# SN74LVC1G86.net
KiCad netlist of a schematic drawn in EasyEDA Pro
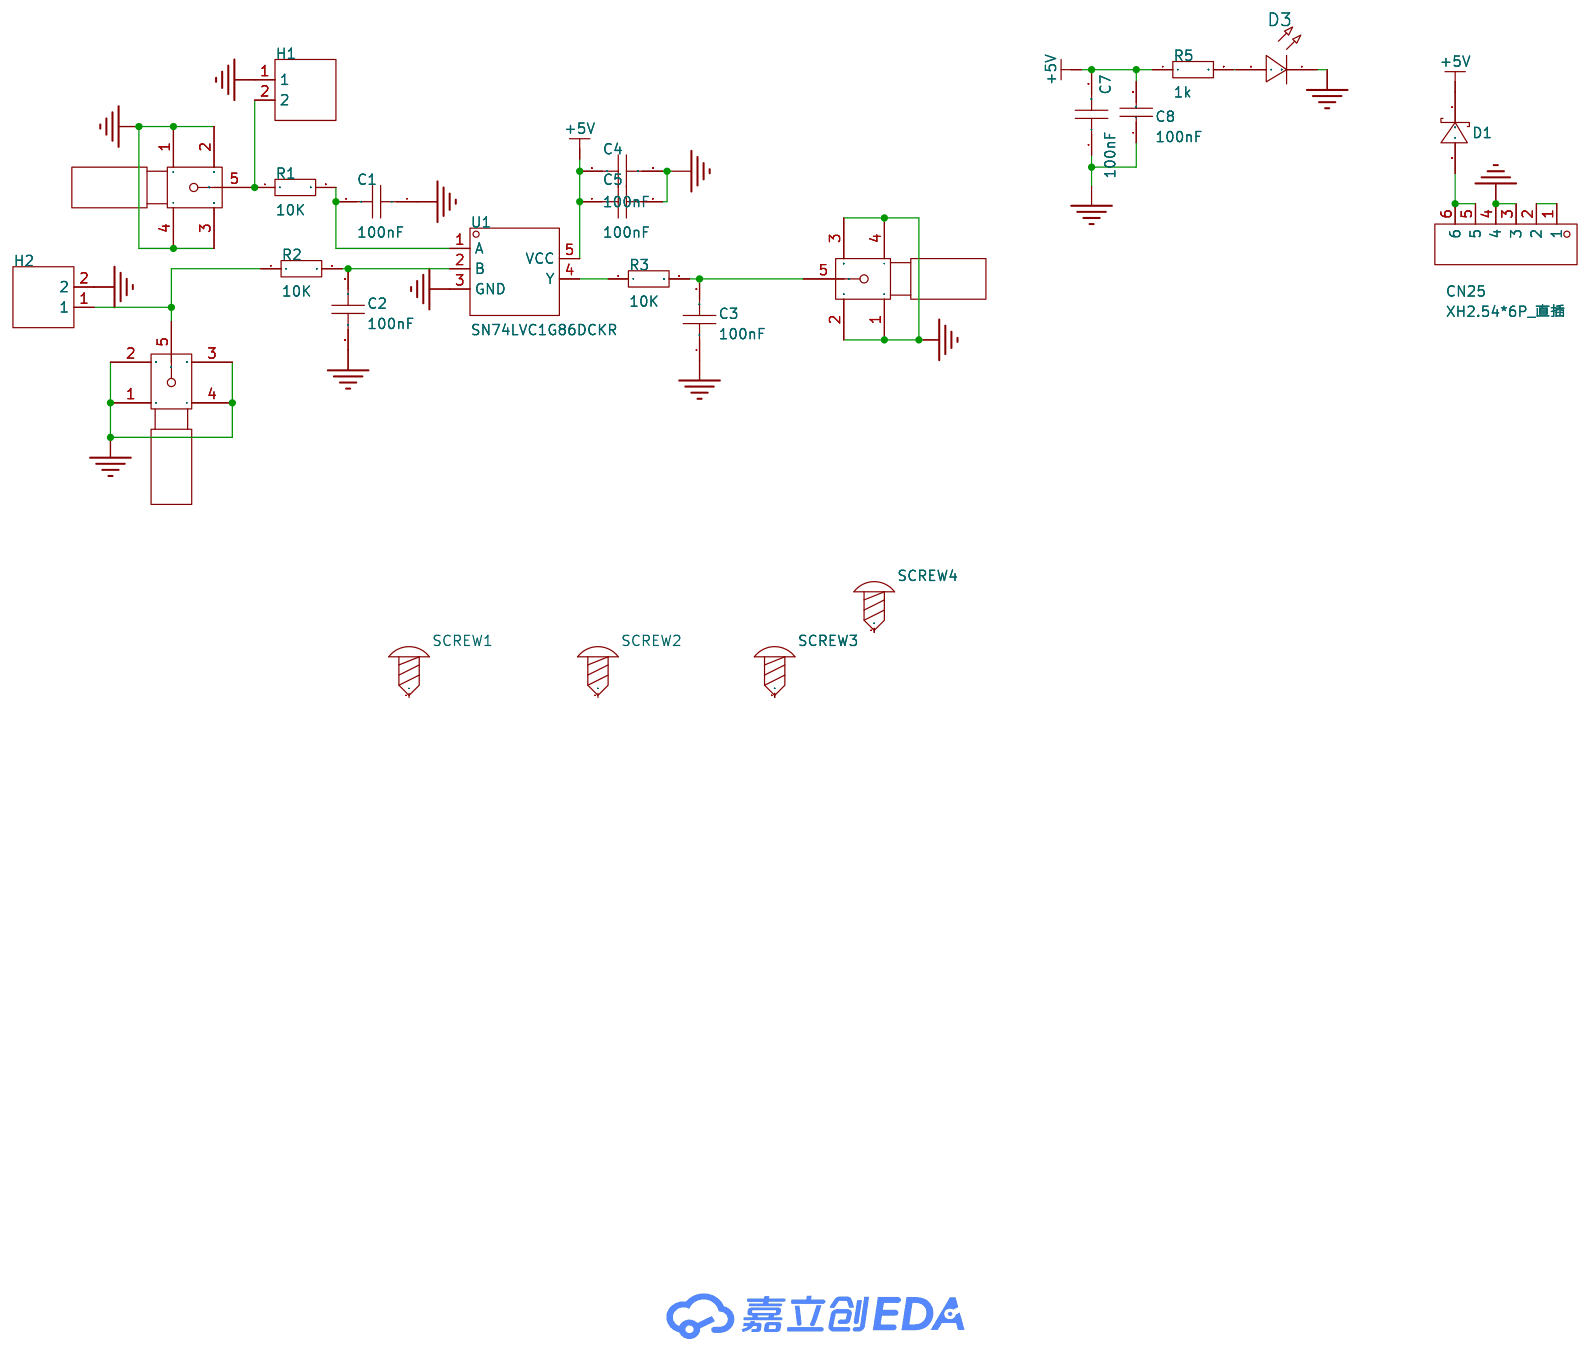
[diagram p0: schematic sheet]

(export (version "E")
  (design (tool "Eeschema 10.0.6"))
  (components
    (comp (ref "C1")
      (value "100nF")
      (footprint "easyedapro:C0805")
      (libsource (lib "easyedapro") (part "CapAcitance"))
    )
    (comp (ref "C2")
      (value "100nF")
      (footprint "easyedapro:C0805")
      (libsource (lib "easyedapro") (part "CapAcitance"))
    )
    (comp (ref "C3")
      (value "100nF")
      (footprint "easyedapro:C0805")
      (libsource (lib "easyedapro") (part "CapAcitance"))
    )
    (comp (ref "C4")
      (value "100nF")
      (footprint "easyedapro:C0805")
      (libsource (lib "easyedapro") (part "CapAcitance"))
    )
    (comp (ref "C5")
      (value "100nF")
      (footprint "easyedapro:C0805")
      (libsource (lib "easyedapro") (part "CapAcitance"))
    )
    (comp (ref "C7")
      (value "100nF")
      (footprint "easyedapro:C0805")
      (libsource (lib "easyedapro") (part "CapAcitance"))
    )
    (comp (ref "C8")
      (value "100nF")
      (footprint "easyedapro:C1210")
      (description "容值:10uF;精度:±10%;额定电压:25V;材质(温度系数):X7R;")
      (fields
        (field (name "Manufacturer Part") "CL32B106KAJNNNE")
        (field (name "Manufacturer") "SAMSUNG(三星)")
      )
      (libsource (lib "easyedapro") (part "CL32B106KAJNNNE"))
    )
    (comp (ref "CN25")
      (value "XH2.54*6P_直插")
      (footprint "easyedapro:CONN-TH_XH2.54-6P")
      (libsource (lib "easyedapro") (part "XH2.54*6P_直插"))
    )
    (comp (ref "D1")
      (value "SD103AWS")
      (footprint "easyedapro:SOD-323_L1.8-W1.3-LS2.5-RD")
      (description "正向压降(Vf):600mV@200mA;直流反向耐压(Vr):40V;整流电流:350mA;")
      (fields (field (name "Manufacturer") "Hottech(合科泰)"))
      (libsource (lib "easyedapro") (part "SD103AWS_C181207"))
    )
    (comp (ref "D3")
      (value "~")
      (footprint "easyedapro:LED_0805")
      (libsource (lib "easyedapro") (part "LED_R"))
    )
    (comp (ref "H1")
      (value "~")
      (footprint "easyedapro:HDR-TH_2P-P2.54-V-M-1")
      (libsource (lib "easyedapro") (part "210S-1*2P L=11.6MMGold-plated black"))
    )
    (comp (ref "H2")
      (value "~")
      (footprint "easyedapro:HDR-TH_2P-P2.54-V-M-1")
      (libsource (lib "easyedapro") (part "210S-1*2P L=11.6MMGold-plated black"))
    )
    (comp (ref "R1") (value "10K") (footprint "easyedapro:R0805") (libsource (lib "easyedapro") (part "电阻")))
    (comp (ref "R2") (value "10K") (footprint "easyedapro:R0805") (libsource (lib "easyedapro") (part "电阻")))
    (comp (ref "R3") (value "10K") (footprint "easyedapro:R0805") (libsource (lib "easyedapro") (part "电阻")))
    (comp (ref "R5") (value "1k") (footprint "easyedapro:R0805") (libsource (lib "easyedapro") (part "电阻")))
    (comp (ref "SCREW1")
      (value "~")
      (footprint "easyedapro:M4螺丝")
      (libsource (lib "easyedapro") (part "螺丝孔"))
    )
    (comp (ref "SCREW2")
      (value "~")
      (footprint "easyedapro:M4螺丝")
      (libsource (lib "easyedapro") (part "螺丝孔"))
    )
    (comp (ref "SCREW3")
      (value "~")
      (footprint "easyedapro:M4螺丝")
      (libsource (lib "easyedapro") (part "螺丝孔"))
    )
    (comp (ref "SCREW4")
      (value "~")
      (footprint "easyedapro:M4螺丝")
      (libsource (lib "easyedapro") (part "螺丝孔"))
    )
    (comp (ref "U1")
      (value "SN74LVC1G86DCKR")
      (footprint "easyedapro:SC-70-5_L2.1-W1.3-P0.65-LS2.1-BR")
      (description "逻辑类型:异或门;通道数:1;工作电压:1.65V~5.5V;静态电流(Iq):10uA;传播延迟(tpd):4ns@5V,50pF;")
      (fields (field (name "Manufacturer") "TI(德州仪器)"))
      (libsource (lib "easyedapro") (part "SN74LVC1G86DCKR"))
    )
    (comp (ref "U17") (value "~") (footprint "easyedapro:SMA") (libsource (lib "easyedapro") (part "SMA")))
    (comp (ref "U18") (value "~") (footprint "easyedapro:SMA") (libsource (lib "easyedapro") (part "SMA")))
    (comp (ref "U19") (value "~") (footprint "easyedapro:SMA") (libsource (lib "easyedapro") (part "SMA")))
  )
  (nets
    (net (code "1") (name "+5V") (class "Default")
      (node (ref "C4") (pin "1") (pinfunction "1_1") (pintype "input"))
      (node (ref "C5") (pin "1") (pinfunction "1_1") (pintype "input"))
      (node (ref "C7") (pin "2") (pinfunction "2_2") (pintype "input"))
      (node (ref "C8") (pin "2") (pinfunction "2_2") (pintype "input"))
      (node (ref "D1") (pin "1") (pinfunction "C_1") (pintype "unspecified"))
      (node (ref "R5") (pin "1") (pinfunction "1_1") (pintype "input"))
      (node (ref "U1") (pin "5") (pinfunction "VCC_5") (pintype "unspecified"))
    )
    (net (code "2") (name "GND") (class "Default")
      (node (ref "C1") (pin "1") (pinfunction "1_1") (pintype "input"))
      (node (ref "C2") (pin "2") (pinfunction "2_2") (pintype "input"))
      (node (ref "C3") (pin "1") (pinfunction "1_1") (pintype "input"))
      (node (ref "C4") (pin "2") (pinfunction "2_2") (pintype "input"))
      (node (ref "C5") (pin "2") (pinfunction "2_2") (pintype "input"))
      (node (ref "C7") (pin "1") (pinfunction "1_1") (pintype "input"))
      (node (ref "C8") (pin "1") (pinfunction "1_1") (pintype "input"))
      (node (ref "CN25") (pin "3") (pinfunction "3_3") (pintype "input"))
      (node (ref "CN25") (pin "4") (pinfunction "4_4") (pintype "input"))
      (node (ref "D3") (pin "1") (pinfunction "C_1") (pintype "input"))
      (node (ref "H1") (pin "1") (pinfunction "1_1") (pintype "unspecified"))
      (node (ref "H2") (pin "2") (pinfunction "2_2") (pintype "unspecified"))
      (node (ref "U1") (pin "3") (pinfunction "GND_3") (pintype "unspecified"))
      (node (ref "U17") (pin "1") (pinfunction "1_1") (pintype "input"))
      (node (ref "U17") (pin "2") (pinfunction "2_2") (pintype "input"))
      (node (ref "U17") (pin "3") (pinfunction "3_3") (pintype "input"))
      (node (ref "U17") (pin "4") (pinfunction "4_4") (pintype "input"))
      (node (ref "U18") (pin "1") (pinfunction "1_1") (pintype "input"))
      (node (ref "U18") (pin "2") (pinfunction "2_2") (pintype "input"))
      (node (ref "U18") (pin "3") (pinfunction "3_3") (pintype "input"))
      (node (ref "U18") (pin "4") (pinfunction "4_4") (pintype "input"))
      (node (ref "U19") (pin "1") (pinfunction "1_1") (pintype "input"))
      (node (ref "U19") (pin "2") (pinfunction "2_2") (pintype "input"))
      (node (ref "U19") (pin "3") (pinfunction "3_3") (pintype "input"))
      (node (ref "U19") (pin "4") (pinfunction "4_4") (pintype "input"))
    )
    (net (code "3") (name "Net-(C3-Pad2)") (class "Default")
      (node (ref "C3") (pin "2") (pinfunction "2_2") (pintype "input"))
      (node (ref "R3") (pin "2") (pinfunction "2_2") (pintype "input"))
      (node (ref "U19") (pin "5") (pinfunction "5_5") (pintype "input"))
    )
    (net (code "4") (name "Net-(CN25-Pad1)") (class "Default")
      (node (ref "CN25") (pin "1") (pinfunction "1_1") (pintype "input"))
      (node (ref "CN25") (pin "2") (pinfunction "2_2") (pintype "input"))
    )
    (net (code "5") (name "Net-(D1-A)") (class "Default")
      (node (ref "CN25") (pin "5") (pinfunction "5_5") (pintype "input"))
      (node (ref "CN25") (pin "6") (pinfunction "6_6") (pintype "input"))
      (node (ref "D1") (pin "2") (pinfunction "A_2") (pintype "unspecified"))
    )
    (net (code "6") (name "Net-(D3-A)") (class "Default")
      (node (ref "D3") (pin "2") (pinfunction "A_2") (pintype "input"))
      (node (ref "R5") (pin "2") (pinfunction "2_2") (pintype "input"))
    )
    (net (code "7") (name "Net-(H1-Pad2)") (class "Default")
      (node (ref "H1") (pin "2") (pinfunction "2_2") (pintype "unspecified"))
      (node (ref "R1") (pin "1") (pinfunction "1_1") (pintype "input"))
      (node (ref "U17") (pin "5") (pinfunction "5_5") (pintype "input"))
    )
    (net (code "8") (name "Net-(H2-Pad1)") (class "Default")
      (node (ref "H2") (pin "1") (pinfunction "1_1") (pintype "unspecified"))
      (node (ref "R2") (pin "1") (pinfunction "1_1") (pintype "input"))
      (node (ref "U18") (pin "5") (pinfunction "5_5") (pintype "input"))
    )
    (net (code "9") (name "Net-(U1-A)") (class "Default")
      (node (ref "C1") (pin "2") (pinfunction "2_2") (pintype "input"))
      (node (ref "R1") (pin "2") (pinfunction "2_2") (pintype "input"))
      (node (ref "U1") (pin "1") (pinfunction "A_1") (pintype "unspecified"))
    )
    (net (code "10") (name "Net-(U1-B)") (class "Default")
      (node (ref "C2") (pin "1") (pinfunction "1_1") (pintype "input"))
      (node (ref "R2") (pin "2") (pinfunction "2_2") (pintype "input"))
      (node (ref "U1") (pin "2") (pinfunction "B_2") (pintype "unspecified"))
    )
    (net (code "11") (name "Net-(U1-Y)") (class "Default")
      (node (ref "R3") (pin "1") (pinfunction "1_1") (pintype "input"))
      (node (ref "U1") (pin "4") (pinfunction "Y_4") (pintype "unspecified"))
    )
    (net (code "12") (name "unconnected-(SCREW1-Pad1)") (class "Default")
      (node (ref "SCREW1") (pin "1") (pinfunction "1_1") (pintype "input"))
    )
    (net (code "13") (name "unconnected-(SCREW2-Pad1)") (class "Default")
      (node (ref "SCREW2") (pin "1") (pinfunction "1_1") (pintype "input"))
    )
    (net (code "14") (name "unconnected-(SCREW3-Pad1)") (class "Default")
      (node (ref "SCREW3") (pin "1") (pinfunction "1_1") (pintype "input"))
    )
    (net (code "15") (name "unconnected-(SCREW4-Pad1)") (class "Default")
      (node (ref "SCREW4") (pin "1") (pinfunction "1_1") (pintype "input"))
    )
  )
)
